# lora-tester.net
KiCad netlist of a schematic drawn in EAGLE
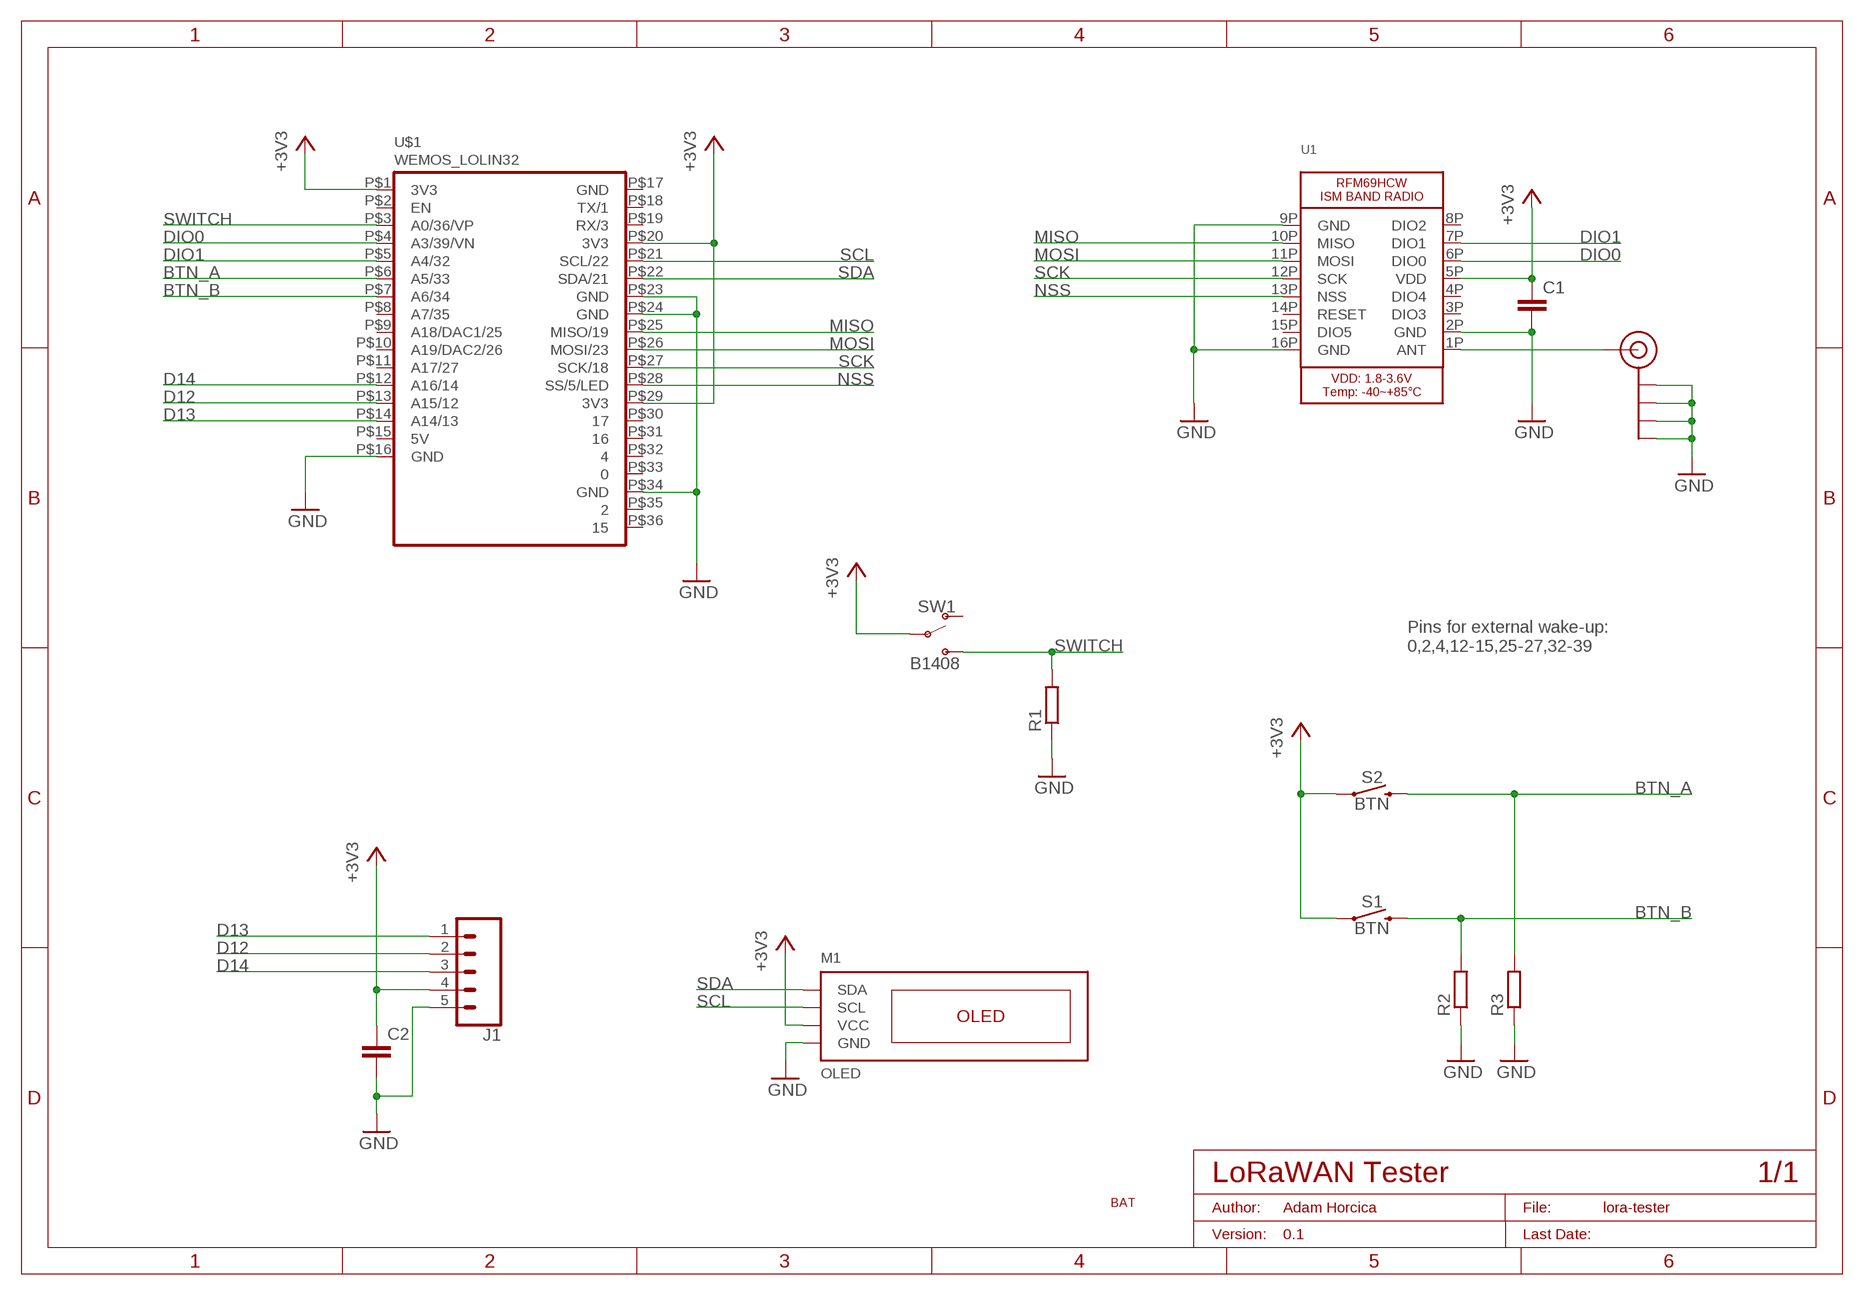
[diagram p0: schematic, sheet 1]

(export (version "E")
  (design (tool "Eeschema 10.0.6"))
  (components
    (comp (ref "BAT")
      (value "BAT")
      (footprint "eagle-import:BAT")
      (libsource (lib "eagle-import") (part "BAT"))
    )
    (comp (ref "C1")
      (value "C-EUC1206")
      (footprint "eagle-import:C1206")
      (libsource (lib "eagle-import") (part "C-EUC1206"))
    )
    (comp (ref "C2")
      (value "C-EUC1206")
      (footprint "eagle-import:C1206")
      (libsource (lib "eagle-import") (part "C-EUC1206"))
    )
    (comp (ref "J$2")
      (value "SMA_EDGE")
      (footprint "eagle-import:SMA-EDGE")
      (libsource (lib "eagle-import") (part "SMA_EDGE"))
    )
    (comp (ref "J1")
      (value "CONN_05PTH_LONGPADS")
      (footprint "eagle-import:1X05_LONGPADS")
      (libsource (lib "eagle-import") (part "CONN_05PTH_LONGPADS"))
    )
    (comp (ref "M1")
      (value "OLED")
      (footprint "eagle-import:OLED")
      (libsource (lib "eagle-import") (part "OLED"))
    )
    (comp (ref "R1")
      (value "R-EU_R0805")
      (footprint "eagle-import:R0805")
      (libsource (lib "eagle-import") (part "R-EU_R0805"))
    )
    (comp (ref "R2")
      (value "R-EU_R0805")
      (footprint "eagle-import:R0805")
      (libsource (lib "eagle-import") (part "R-EU_R0805"))
    )
    (comp (ref "R3")
      (value "R-EU_R0805")
      (footprint "eagle-import:R0805")
      (libsource (lib "eagle-import") (part "R-EU_R0805"))
    )
    (comp (ref "S1")
      (value "BTN")
      (footprint "eagle-import:TACTILE_SWITCH_SMD_6.2MM_TALL")
      (libsource (lib "eagle-import") (part "MOMENTARY-SWITCH-SPST-SMD-6.2MM-TALL"))
    )
    (comp (ref "S2")
      (value "BTN")
      (footprint "eagle-import:TACTILE_SWITCH_SMD_6.2MM_TALL")
      (libsource (lib "eagle-import") (part "MOMENTARY-SWITCH-SPST-SMD-6.2MM-TALL"))
    )
    (comp (ref "SW1")
      (value "B1408")
      (footprint "eagle-import:P-B1408")
      (libsource (lib "eagle-import") (part "SL19-121P-B1408"))
    )
    (comp (ref "U$1")
      (value "WEMOS_LOLIN32")
      (footprint "eagle-import:WEMOS_LOLIN32")
      (libsource (lib "eagle-import") (part "WEMOS_LOLIN32"))
    )
    (comp (ref "U1")
      (value "RFM69HCW_SMT")
      (footprint "eagle-import:RFMHCW_SMT")
      (libsource (lib "eagle-import") (part "RFM69HCW_SMT"))
    )
  )
  (nets
    (net (code "1") (name "+3V3") (class "Default")
      (node (ref "C1") (pin "1") (pinfunction "1_1") (pintype "passive"))
      (node (ref "C2") (pin "1") (pinfunction "1_1") (pintype "passive"))
      (node (ref "J1") (pin "4") (pinfunction "4_4") (pintype "passive"))
      (node (ref "M1") (pin "VCC") (pinfunction "VCC_VCC") (pintype "bidirectional"))
      (node (ref "S1") (pin "A2") (pinfunction "1_A2") (pintype "passive"))
      (node (ref "S2") (pin "A2") (pinfunction "1_A2") (pintype "passive"))
      (node (ref "SW1") (pin "P") (pinfunction "P_P") (pintype "passive"))
      (node (ref "U$1") (pin "P$1") (pinfunction "3V3_P$1") (pintype "bidirectional"))
      (node (ref "U$1") (pin "P$20") (pinfunction "3V3_P$20") (pintype "bidirectional"))
      (node (ref "U$1") (pin "P$29") (pinfunction "3V3_P$29") (pintype "bidirectional"))
      (node (ref "U1") (pin "5P") (pinfunction "VDD_5P") (pintype "power_in"))
    )
    (net (code "2") (name "/BTN_A") (class "Default")
      (node (ref "R3") (pin "2") (pinfunction "2_2") (pintype "passive"))
      (node (ref "S2") (pin "B2") (pinfunction "2_B2") (pintype "passive"))
      (node (ref "U$1") (pin "P$6") (pinfunction "A5/33_P$6") (pintype "bidirectional"))
    )
    (net (code "3") (name "/BTN_B") (class "Default")
      (node (ref "R2") (pin "2") (pinfunction "2_2") (pintype "passive"))
      (node (ref "S1") (pin "B2") (pinfunction "2_B2") (pintype "passive"))
      (node (ref "U$1") (pin "P$7") (pinfunction "A6/34_P$7") (pintype "bidirectional"))
    )
    (net (code "4") (name "/D12") (class "Default")
      (node (ref "J1") (pin "2") (pinfunction "2_2") (pintype "passive"))
      (node (ref "U$1") (pin "P$13") (pinfunction "A15/12_P$13") (pintype "bidirectional"))
    )
    (net (code "5") (name "/D13") (class "Default")
      (node (ref "J1") (pin "1") (pinfunction "1_1") (pintype "passive"))
      (node (ref "U$1") (pin "P$14") (pinfunction "A14/13_P$14") (pintype "bidirectional"))
    )
    (net (code "6") (name "/D14") (class "Default")
      (node (ref "J1") (pin "3") (pinfunction "3_3") (pintype "passive"))
      (node (ref "U$1") (pin "P$12") (pinfunction "A16/14_P$12") (pintype "bidirectional"))
    )
    (net (code "7") (name "/DIO0") (class "Default")
      (node (ref "U$1") (pin "P$4") (pinfunction "A3/39/VN_P$4") (pintype "bidirectional"))
      (node (ref "U1") (pin "6P") (pinfunction "DIO0_6P") (pintype "bidirectional"))
    )
    (net (code "8") (name "/DIO1") (class "Default")
      (node (ref "U$1") (pin "P$5") (pinfunction "A4/32_P$5") (pintype "bidirectional"))
      (node (ref "U1") (pin "7P") (pinfunction "DIO1_7P") (pintype "bidirectional"))
    )
    (net (code "9") (name "/MISO") (class "Default")
      (node (ref "U$1") (pin "P$25") (pinfunction "MISO/19_P$25") (pintype "bidirectional"))
      (node (ref "U1") (pin "10P") (pinfunction "MISO_10P") (pintype "output"))
    )
    (net (code "10") (name "/MOSI") (class "Default")
      (node (ref "U$1") (pin "P$26") (pinfunction "MOSI/23_P$26") (pintype "bidirectional"))
      (node (ref "U1") (pin "11P") (pinfunction "MOSI_11P") (pintype "input"))
    )
    (net (code "11") (name "/NSS") (class "Default")
      (node (ref "U$1") (pin "P$28") (pinfunction "SS/5/LED_P$28") (pintype "bidirectional"))
      (node (ref "U1") (pin "13P") (pinfunction "NSS_13P") (pintype "input"))
    )
    (net (code "12") (name "/SCK") (class "Default")
      (node (ref "U$1") (pin "P$27") (pinfunction "SCK/18_P$27") (pintype "bidirectional"))
      (node (ref "U1") (pin "12P") (pinfunction "SCK_12P") (pintype "input"))
    )
    (net (code "13") (name "/SCL") (class "Default")
      (node (ref "M1") (pin "SCL") (pinfunction "SCL_SCL") (pintype "bidirectional"))
      (node (ref "U$1") (pin "P$21") (pinfunction "SCL/22_P$21") (pintype "bidirectional"))
    )
    (net (code "14") (name "/SDA") (class "Default")
      (node (ref "M1") (pin "SDA") (pinfunction "SDA_SDA") (pintype "bidirectional"))
      (node (ref "U$1") (pin "P$22") (pinfunction "SDA/21_P$22") (pintype "bidirectional"))
    )
    (net (code "15") (name "/SWITCH") (class "Default")
      (node (ref "R1") (pin "2") (pinfunction "2_2") (pintype "passive"))
      (node (ref "SW1") (pin "S") (pinfunction "S_S") (pintype "passive"))
      (node (ref "U$1") (pin "P$3") (pinfunction "A0/36/VP_P$3") (pintype "bidirectional"))
    )
    (net (code "16") (name "GND") (class "Default")
      (node (ref "C1") (pin "2") (pinfunction "2_2") (pintype "passive"))
      (node (ref "C2") (pin "2") (pinfunction "2_2") (pintype "passive"))
      (node (ref "J$2") (pin "GND@0") (pinfunction "GND_GND@0") (pintype "bidirectional"))
      (node (ref "J$2") (pin "GND@1") (pinfunction "GND_GND@1") (pintype "bidirectional"))
      (node (ref "J$2") (pin "GND@2") (pinfunction "GND_GND@2") (pintype "bidirectional"))
      (node (ref "J$2") (pin "GND@3") (pinfunction "GND_GND@3") (pintype "bidirectional"))
      (node (ref "J1") (pin "5") (pinfunction "5_5") (pintype "passive"))
      (node (ref "M1") (pin "GND") (pinfunction "GND_GND") (pintype "bidirectional"))
      (node (ref "R1") (pin "1") (pinfunction "1_1") (pintype "passive"))
      (node (ref "R2") (pin "1") (pinfunction "1_1") (pintype "passive"))
      (node (ref "R3") (pin "1") (pinfunction "1_1") (pintype "passive"))
      (node (ref "U$1") (pin "P$16") (pinfunction "GND_P$16") (pintype "bidirectional"))
      (node (ref "U$1") (pin "P$23") (pinfunction "GND_P$23") (pintype "bidirectional"))
      (node (ref "U$1") (pin "P$24") (pinfunction "GND_P$24") (pintype "bidirectional"))
      (node (ref "U$1") (pin "P$34") (pinfunction "GND_P$34") (pintype "bidirectional"))
      (node (ref "U1") (pin "16P") (pinfunction "GND_16P") (pintype "power_in"))
      (node (ref "U1") (pin "2P") (pinfunction "GND_2P") (pintype "power_in"))
      (node (ref "U1") (pin "9P") (pinfunction "GND_9P") (pintype "power_in"))
    )
    (net (code "17") (name "Net-(J$2-SIGNAL)") (class "Default")
      (node (ref "J$2") (pin "SIG") (pinfunction "SIGNAL_SIG") (pintype "bidirectional"))
      (node (ref "U1") (pin "1P") (pinfunction "ANT_1P") (pintype "bidirectional"))
    )
    (net (code "18") (name "unconnected-(SW1-PadO)") (class "Default")
      (node (ref "SW1") (pin "O") (pinfunction "O_O") (pintype "passive"))
    )
    (net (code "19") (name "unconnected-(U$1-0-PadP$33)") (class "Default")
      (node (ref "U$1") (pin "P$33") (pinfunction "0_P$33") (pintype "bidirectional"))
    )
    (net (code "20") (name "unconnected-(U$1-2-PadP$35)") (class "Default")
      (node (ref "U$1") (pin "P$35") (pinfunction "2_P$35") (pintype "bidirectional"))
    )
    (net (code "21") (name "unconnected-(U$1-4-PadP$32)") (class "Default")
      (node (ref "U$1") (pin "P$32") (pinfunction "4_P$32") (pintype "bidirectional"))
    )
    (net (code "22") (name "unconnected-(U$1-5V-PadP$15)") (class "Default")
      (node (ref "U$1") (pin "P$15") (pinfunction "5V_P$15") (pintype "bidirectional"))
    )
    (net (code "23") (name "unconnected-(U$1-15-PadP$36)") (class "Default")
      (node (ref "U$1") (pin "P$36") (pinfunction "15_P$36") (pintype "bidirectional"))
    )
    (net (code "24") (name "unconnected-(U$1-16-PadP$31)") (class "Default")
      (node (ref "U$1") (pin "P$31") (pinfunction "16_P$31") (pintype "bidirectional"))
    )
    (net (code "25") (name "unconnected-(U$1-17-PadP$30)") (class "Default")
      (node (ref "U$1") (pin "P$30") (pinfunction "17_P$30") (pintype "bidirectional"))
    )
    (net (code "26") (name "unconnected-(U$1-A7{slash}35-PadP$8)") (class "Default")
      (node (ref "U$1") (pin "P$8") (pinfunction "A7/35_P$8") (pintype "bidirectional"))
    )
    (net (code "27") (name "unconnected-(U$1-A17{slash}27-PadP$11)") (class "Default")
      (node (ref "U$1") (pin "P$11") (pinfunction "A17/27_P$11") (pintype "bidirectional"))
    )
    (net (code "28") (name "unconnected-(U$1-A18{slash}DAC1{slash}25-PadP$9)") (class "Default")
      (node (ref "U$1") (pin "P$9") (pinfunction "A18/DAC1/25_P$9") (pintype "bidirectional"))
    )
    (net (code "29") (name "unconnected-(U$1-A19{slash}DAC2{slash}26-PadP$10)") (class "Default")
      (node (ref "U$1") (pin "P$10") (pinfunction "A19/DAC2/26_P$10") (pintype "bidirectional"))
    )
    (net (code "30") (name "unconnected-(U$1-EN-PadP$2)") (class "Default")
      (node (ref "U$1") (pin "P$2") (pinfunction "EN_P$2") (pintype "bidirectional"))
    )
    (net (code "31") (name "unconnected-(U$1-GND-PadP$17)") (class "Default")
      (node (ref "U$1") (pin "P$17") (pinfunction "GND_P$17") (pintype "bidirectional"))
    )
    (net (code "32") (name "unconnected-(U$1-RX{slash}3-PadP$19)") (class "Default")
      (node (ref "U$1") (pin "P$19") (pinfunction "RX/3_P$19") (pintype "bidirectional"))
    )
    (net (code "33") (name "unconnected-(U$1-TX{slash}1-PadP$18)") (class "Default")
      (node (ref "U$1") (pin "P$18") (pinfunction "TX/1_P$18") (pintype "bidirectional"))
    )
    (net (code "34") (name "unconnected-(U1-DIO2-Pad8P)") (class "Default")
      (node (ref "U1") (pin "8P") (pinfunction "DIO2_8P") (pintype "bidirectional"))
    )
    (net (code "35") (name "unconnected-(U1-DIO3-Pad3P)") (class "Default")
      (node (ref "U1") (pin "3P") (pinfunction "DIO3_3P") (pintype "bidirectional"))
    )
    (net (code "36") (name "unconnected-(U1-DIO4-Pad4P)") (class "Default")
      (node (ref "U1") (pin "4P") (pinfunction "DIO4_4P") (pintype "bidirectional"))
    )
    (net (code "37") (name "unconnected-(U1-DIO5-Pad15P)") (class "Default")
      (node (ref "U1") (pin "15P") (pinfunction "DIO5_15P") (pintype "bidirectional"))
    )
    (net (code "38") (name "unconnected-(U1-RESET-Pad14P)") (class "Default")
      (node (ref "U1") (pin "14P") (pinfunction "RESET_14P") (pintype "input"))
    )
  )
)
